# 09-RF_SUBG.net
KiCad netlist of a schematic drawn in Altium Designer
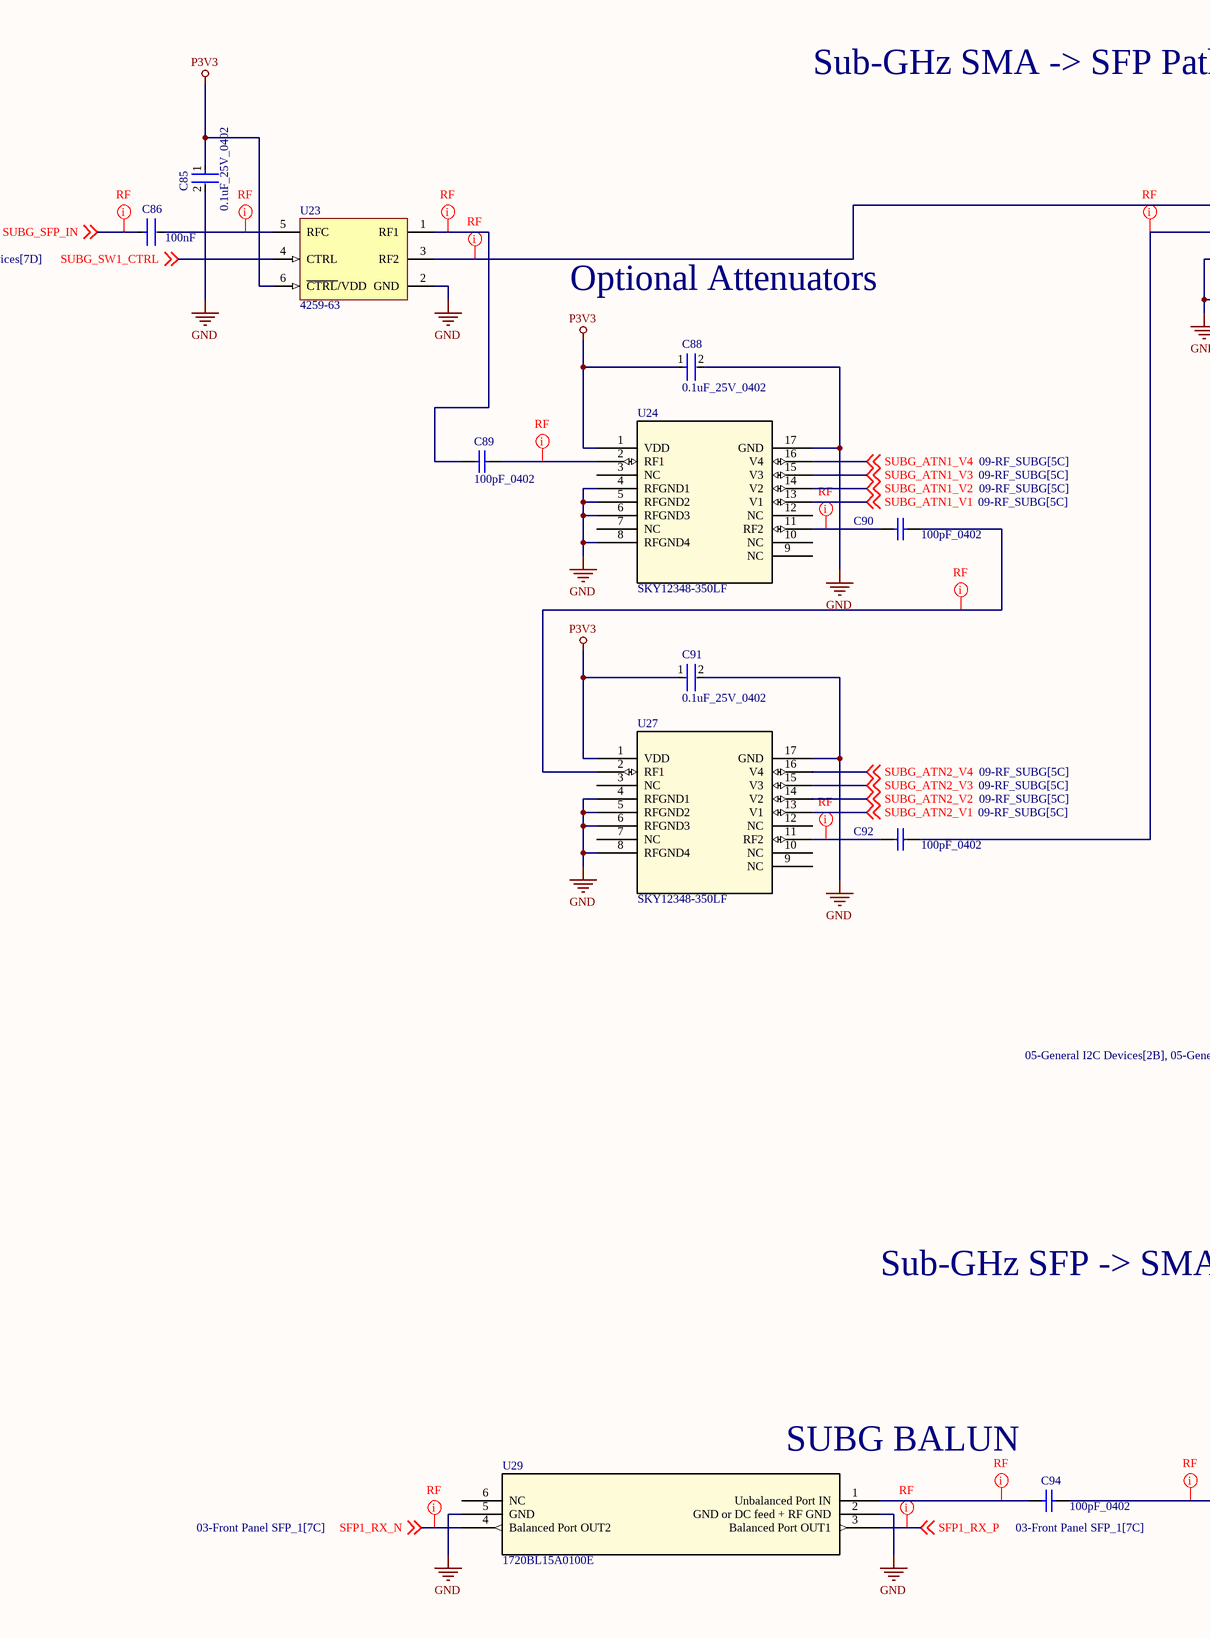
[diagram p0: 09-RF_SUBG.SchDoc, left]
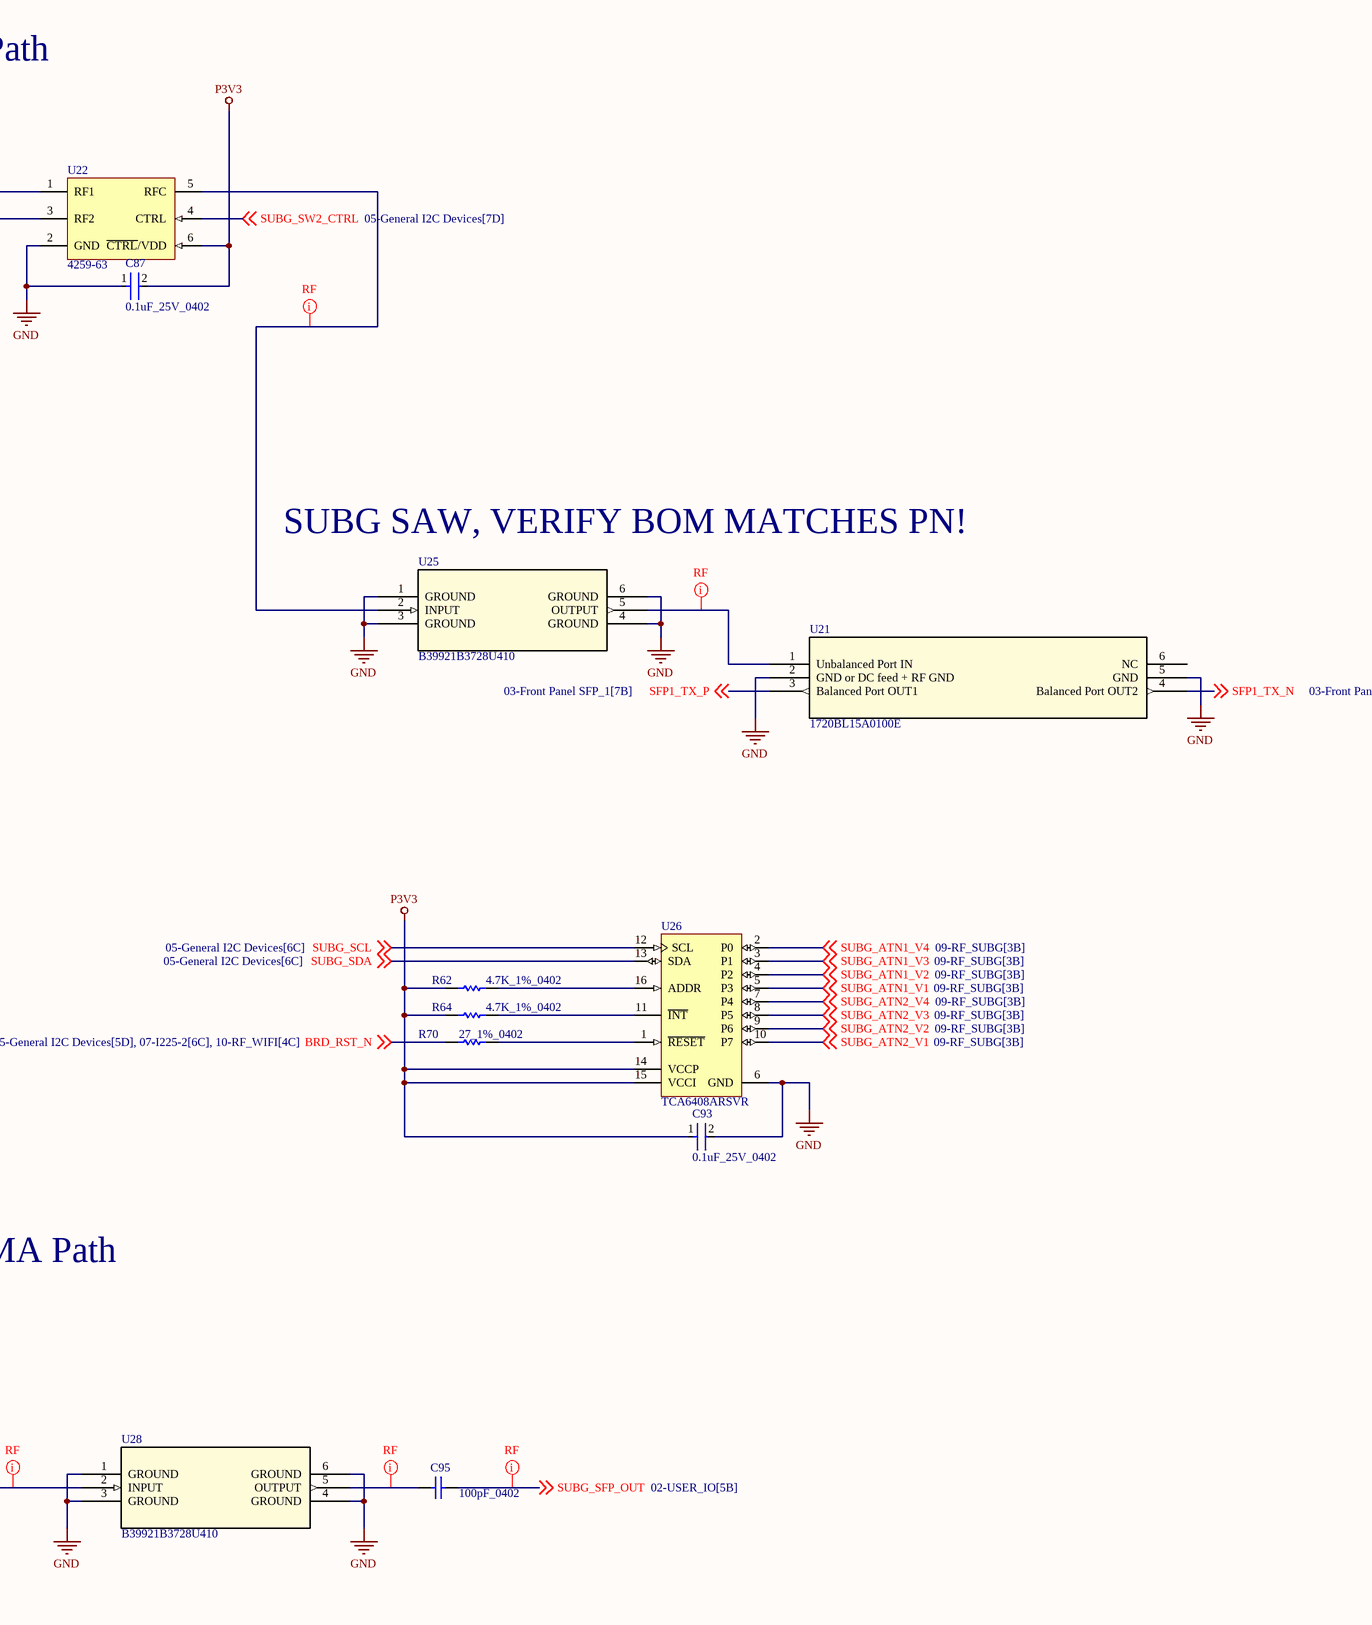
[diagram p1: 09-RF_SUBG.SchDoc, right]

(export (version "E")
  (design (tool "Eeschema 10.0.6"))
  (components
    (comp (ref "C85")
      (value "0.1uF_25V_0402")
      (footprint "FP-0402-L_1_0_1-W_0_5_0_1-IPC_C")
      (description "General Purpose Ceramic Capacitor, 0402, 100nF, 10%, X7R, 15%, 25V")
      (fields (field (name "VOLTAGE") "25V") (field (name "TOLERANCE") "10%"))
      (libsource (lib "Altium Content Vault") (part "b4654b650e69147ec39a6b967a45e02"))
    )
    (comp (ref "C86")
      (value "100nF")
      (footprint "FP-0402-L_1_0_0_05-W_0_5-IPC_B")
      (description "None")
      (fields (field (name "TOLERANCE") "10%"))
      (libsource (lib "") (part "b4654b650e69147ec39a6b967a45e02_1"))
    )
    (comp (ref "C87")
      (value "0.1uF_25V_0402")
      (footprint "FP-0402-L_1_0_1-W_0_5_0_1-IPC_C")
      (description "General Purpose Ceramic Capacitor, 0402, 100nF, 10%, X7R, 15%, 25V")
      (fields (field (name "VOLTAGE") "25V") (field (name "TOLERANCE") "10%"))
      (libsource (lib "Altium Content Vault") (part "b4654b650e69147ec39a6b967a45e02"))
    )
    (comp (ref "C88")
      (value "0.1uF_25V_0402")
      (footprint "FP-0402-L_1_0_1-W_0_5_0_1-IPC_C")
      (description "General Purpose Ceramic Capacitor, 0402, 100nF, 10%, X7R, 15%, 25V")
      (fields (field (name "VOLTAGE") "25V") (field (name "TOLERANCE") "10%"))
      (libsource (lib "Altium Content Vault") (part "b4654b650e69147ec39a6b967a45e02"))
    )
    (comp (ref "C89")
      (value "100pF_0402")
      (footprint "CAPC1005X55X25ML05T10")
      (fields (field (name "MANUFACTURER") "Murata") (field (name "PART NUMBER") "GRM1555C1H101JA01D"))
      (libsource (lib "Altium Content Vault") (part "CAP"))
    )
    (comp (ref "C90")
      (value "100pF_0402")
      (footprint "CAPC1005X55X25ML05T10")
      (fields (field (name "MANUFACTURER") "Murata") (field (name "PART NUMBER") "GRM1555C1H101JA01D"))
      (libsource (lib "Altium Content Vault") (part "CAP"))
    )
    (comp (ref "C91")
      (value "0.1uF_25V_0402")
      (footprint "FP-0402-L_1_0_1-W_0_5_0_1-IPC_C")
      (description "General Purpose Ceramic Capacitor, 0402, 100nF, 10%, X7R, 15%, 25V")
      (fields (field (name "VOLTAGE") "25V") (field (name "TOLERANCE") "10%"))
      (libsource (lib "Altium Content Vault") (part "b4654b650e69147ec39a6b967a45e02"))
    )
    (comp (ref "C92")
      (value "100pF_0402")
      (footprint "CAPC1005X55X25ML05T10")
      (fields (field (name "MANUFACTURER") "Murata") (field (name "PART NUMBER") "GRM1555C1H101JA01D"))
      (libsource (lib "Altium Content Vault") (part "CAP"))
    )
    (comp (ref "C93")
      (value "0.1uF_25V_0402")
      (footprint "FP-0402-L_1_0_1-W_0_5_0_1-IPC_C")
      (description "General Purpose Ceramic Capacitor, 0402, 100nF, 10%, X7R, 15%, 25V")
      (fields (field (name "VOLTAGE") "25V") (field (name "TOLERANCE") "10%"))
      (libsource (lib "Altium Content Vault") (part "b4654b650e69147ec39a6b967a45e02"))
    )
    (comp (ref "C94")
      (value "100pF_0402")
      (footprint "CAPC1005X55X25ML05T10")
      (fields (field (name "MANUFACTURER") "Murata") (field (name "PART NUMBER") "GRM1555C1H101JA01D"))
      (libsource (lib "Altium Content Vault") (part "CAP"))
    )
    (comp (ref "C95")
      (value "100pF_0402")
      (footprint "CAPC1005X55X25ML05T10")
      (fields (field (name "MANUFACTURER") "Murata") (field (name "PART NUMBER") "GRM1555C1H101JA01D"))
      (libsource (lib "Altium Content Vault") (part "CAP"))
    )
    (comp (ref "R62")
      (value "4.7K_1%_0402")
      (footprint "RESC1005X40X25NL10T10")
      (fields (field (name "MANUFACTURER") "Bourns") (field (name "PART NUMBER") "CR0402-FX-4701GLF"))
      (libsource (lib "Altium Content Vault") (part "RES"))
    )
    (comp (ref "R64")
      (value "4.7K_1%_0402")
      (footprint "RESC1005X40X25NL10T10")
      (fields (field (name "MANUFACTURER") "Bourns") (field (name "PART NUMBER") "CR0402-FX-4701GLF"))
      (libsource (lib "Altium Content Vault") (part "RES"))
    )
    (comp (ref "R70")
      (value "27_1%_0402")
      (footprint "RESC1005X40X25NL05T05")
      (fields (field (name "PART NUMBER") "CRCW040227R0FKED") (field (name "MANUFACTURER") "Vishay Dale"))
      (libsource (lib "Altium Content Vault") (part "RES"))
    )
    (comp (ref "U21")
      (value "1720BL15A0100E")
      (footprint "SMT_15B0050E_JOT")
      (description "No Description Available")
      (libsource (lib "") (part "1720BL15A0100E_1"))
    )
    (comp (ref "U22")
      (value "4259-63")
      (footprint "PERE-SC-70-6_M")
      (description "IC RF Switch SPDT, 50 Ohm, 6-Pin SC70, RoHS, Tape and Reel")
      (fields (field (name "MANUFACTURER") "Peregrine Semiconductor"))
      (libsource (lib "Altium Content Vault") (part "PERE-PE4259-6"))
    )
    (comp (ref "U23")
      (value "4259-63")
      (footprint "PERE-SC-70-6_M")
      (description "IC RF Switch SPDT, 50 Ohm, 6-Pin SC70, RoHS, Tape and Reel")
      (fields (field (name "MANUFACTURER") "Peregrine Semiconductor"))
      (libsource (lib "") (part "PERE-PE4259-6_1"))
    )
    (comp (ref "U24")
      (value "SKY12348-350LF")
      (footprint "SKY12348-350LF_SKY")
      (description "No Description Available")
      (libsource (lib "SKY12348-350LF") (part "SKY12348-350LF"))
    )
    (comp (ref "U25")
      (value "B39921B3728U410")
      (footprint "B39162B3913U410_QUA")
      (description "No Description Available")
      (libsource (lib "B39162B3913U410") (part "B39162B3913U410"))
    )
    (comp (ref "U26")
      (value "TCA6408ARSVR")
      (footprint "RSV0016A_V")
      (fields (field (name "MANUFACTURER") "Texas Instruments"))
      (libsource (lib "Altium Content Vault") (part "TI-TCA6408A-UQFN_RSV-16"))
    )
    (comp (ref "U27")
      (value "SKY12348-350LF")
      (footprint "SKY12348-350LF_SKY")
      (description "No Description Available")
      (libsource (lib "SKY12348-350LF") (part "SKY12348-350LF"))
    )
    (comp (ref "U28")
      (value "B39921B3728U410")
      (footprint "B39162B3913U410_QUA")
      (description "No Description Available")
      (libsource (lib "B39162B3913U410") (part "B39162B3913U410"))
    )
    (comp (ref "U29")
      (value "1720BL15A0100E")
      (footprint "SMT_15B0050E_JOT")
      (description "No Description Available")
      (libsource (lib "1720BL15A0100E") (part "1720BL15A0100E"))
    )
  )
  (nets
    (net (code "1") (name "BRD_RST_N") (class "Default")
      (node (ref "R70") (pin "1") (pinfunction "1_1") (pintype "passive"))
    )
    (net (code "2") (name "GND") (class "Default")
      (node (ref "C85") (pin "2") (pinfunction "2_2") (pintype "passive"))
      (node (ref "C87") (pin "1") (pinfunction "1_1") (pintype "passive"))
      (node (ref "C88") (pin "2") (pinfunction "2_2") (pintype "passive"))
      (node (ref "C91") (pin "2") (pinfunction "2_2") (pintype "passive"))
      (node (ref "C93") (pin "2") (pinfunction "2_2") (pintype "passive"))
      (node (ref "U21") (pin "2") (pinfunction "GND_or_DC_feed_+_RF_GND_2") (pintype "power_in"))
      (node (ref "U21") (pin "5") (pinfunction "GND_5") (pintype "power_in"))
      (node (ref "U22") (pin "2") (pinfunction "GND_2") (pintype "power_in"))
      (node (ref "U23") (pin "2") (pinfunction "GND_2") (pintype "power_in"))
      (node (ref "U24") (pin "17") (pinfunction "GND_17") (pintype "power_in"))
      (node (ref "U24") (pin "4") (pinfunction "RFGND1_4") (pintype "power_in"))
      (node (ref "U24") (pin "5") (pinfunction "RFGND2_5") (pintype "power_in"))
      (node (ref "U24") (pin "6") (pinfunction "RFGND3_6") (pintype "power_in"))
      (node (ref "U24") (pin "8") (pinfunction "RFGND4_8") (pintype "power_in"))
      (node (ref "U25") (pin "1") (pinfunction "GROUND_1") (pintype "power_in"))
      (node (ref "U25") (pin "3") (pinfunction "GROUND_3") (pintype "power_in"))
      (node (ref "U25") (pin "4") (pinfunction "GROUND_4") (pintype "power_in"))
      (node (ref "U25") (pin "6") (pinfunction "GROUND_6") (pintype "power_in"))
      (node (ref "U26") (pin "6") (pinfunction "GND_6") (pintype "power_in"))
      (node (ref "U27") (pin "17") (pinfunction "GND_17") (pintype "power_in"))
      (node (ref "U27") (pin "4") (pinfunction "RFGND1_4") (pintype "power_in"))
      (node (ref "U27") (pin "5") (pinfunction "RFGND2_5") (pintype "power_in"))
      (node (ref "U27") (pin "6") (pinfunction "RFGND3_6") (pintype "power_in"))
      (node (ref "U27") (pin "8") (pinfunction "RFGND4_8") (pintype "power_in"))
      (node (ref "U28") (pin "1") (pinfunction "GROUND_1") (pintype "power_in"))
      (node (ref "U28") (pin "3") (pinfunction "GROUND_3") (pintype "power_in"))
      (node (ref "U28") (pin "4") (pinfunction "GROUND_4") (pintype "power_in"))
      (node (ref "U28") (pin "6") (pinfunction "GROUND_6") (pintype "power_in"))
      (node (ref "U29") (pin "2") (pinfunction "GND_or_DC_feed_+_RF_GND_2") (pintype "power_in"))
      (node (ref "U29") (pin "5") (pinfunction "GND_5") (pintype "power_in"))
    )
    (net (code "3") (name "Net-(U21-Unbalanced_Port_IN)") (class "Default")
      (node (ref "U21") (pin "1") (pinfunction "Unbalanced_Port_IN_1") (pintype "passive"))
      (node (ref "U25") (pin "5") (pinfunction "OUTPUT_5") (pintype "output"))
    )
    (net (code "4") (name "Net-(U22-RF1)") (class "Default")
      (node (ref "U22") (pin "1") (pinfunction "RF1_1") (pintype "passive"))
      (node (ref "U23") (pin "3") (pinfunction "RF2_3") (pintype "passive"))
    )
    (net (code "5") (name "Net-(U22-RF2)") (class "Default")
      (node (ref "C92") (pin "2") (pinfunction "2_2") (pintype "passive"))
      (node (ref "U22") (pin "3") (pinfunction "RF2_3") (pintype "passive"))
    )
    (net (code "6") (name "Net-(U22-RFC)") (class "Default")
      (node (ref "U22") (pin "5") (pinfunction "RFC_5") (pintype "passive"))
      (node (ref "U25") (pin "2") (pinfunction "INPUT_2") (pintype "input"))
    )
    (net (code "7") (name "Net-(U23-RF1)") (class "Default")
      (node (ref "C89") (pin "1") (pinfunction "1_1") (pintype "passive"))
      (node (ref "U23") (pin "1") (pinfunction "RF1_1") (pintype "passive"))
    )
    (net (code "8") (name "Net-(U23-RFC)") (class "Default")
      (node (ref "C86") (pin "2") (pinfunction "2_2") (pintype "passive"))
      (node (ref "U23") (pin "5") (pinfunction "RFC_5") (pintype "passive"))
    )
    (net (code "9") (name "Net-(U24-RF1)") (class "Default")
      (node (ref "C89") (pin "2") (pinfunction "2_2") (pintype "passive"))
      (node (ref "U24") (pin "2") (pinfunction "RF1_2") (pintype "bidirectional"))
    )
    (net (code "10") (name "Net-(U24-RF2)") (class "Default")
      (node (ref "C90") (pin "1") (pinfunction "1_1") (pintype "passive"))
      (node (ref "U24") (pin "11") (pinfunction "RF2_11") (pintype "bidirectional"))
    )
    (net (code "11") (name "Net-(U26-ADDR)") (class "Default")
      (node (ref "R62") (pin "1") (pinfunction "1_1") (pintype "passive"))
      (node (ref "U26") (pin "16") (pinfunction "ADDR_16") (pintype "input"))
    )
    (net (code "12") (name "Net-(U26-~{INT})") (class "Default")
      (node (ref "R64") (pin "1") (pinfunction "1_1") (pintype "passive"))
      (node (ref "U26") (pin "11") (pinfunction "~{INT}_11") (pintype "open_collector"))
    )
    (net (code "13") (name "Net-(U26-~{RESET})") (class "Default")
      (node (ref "R70") (pin "2") (pinfunction "2_2") (pintype "passive"))
      (node (ref "U26") (pin "1") (pinfunction "~{RESET}_1") (pintype "input"))
    )
    (net (code "14") (name "Net-(U27-RF1)") (class "Default")
      (node (ref "C90") (pin "2") (pinfunction "2_2") (pintype "passive"))
      (node (ref "U27") (pin "2") (pinfunction "RF1_2") (pintype "bidirectional"))
    )
    (net (code "15") (name "Net-(U27-RF2)") (class "Default")
      (node (ref "C92") (pin "1") (pinfunction "1_1") (pintype "passive"))
      (node (ref "U27") (pin "11") (pinfunction "RF2_11") (pintype "bidirectional"))
    )
    (net (code "16") (name "Net-(U28-INPUT)") (class "Default")
      (node (ref "C94") (pin "2") (pinfunction "2_2") (pintype "passive"))
      (node (ref "U28") (pin "2") (pinfunction "INPUT_2") (pintype "input"))
    )
    (net (code "17") (name "Net-(U28-OUTPUT)") (class "Default")
      (node (ref "C95") (pin "1") (pinfunction "1_1") (pintype "passive"))
      (node (ref "U28") (pin "5") (pinfunction "OUTPUT_5") (pintype "output"))
    )
    (net (code "18") (name "Net-(U29-Unbalanced_Port_IN)") (class "Default")
      (node (ref "C94") (pin "1") (pinfunction "1_1") (pintype "passive"))
      (node (ref "U29") (pin "1") (pinfunction "Unbalanced_Port_IN_1") (pintype "passive"))
    )
    (net (code "19") (name "P3V3") (class "Default")
      (node (ref "C85") (pin "1") (pinfunction "1_1") (pintype "passive"))
      (node (ref "C87") (pin "2") (pinfunction "2_2") (pintype "passive"))
      (node (ref "C88") (pin "1") (pinfunction "1_1") (pintype "passive"))
      (node (ref "C91") (pin "1") (pinfunction "1_1") (pintype "passive"))
      (node (ref "C93") (pin "1") (pinfunction "1_1") (pintype "passive"))
      (node (ref "R62") (pin "2") (pinfunction "2_2") (pintype "passive"))
      (node (ref "R64") (pin "2") (pinfunction "2_2") (pintype "passive"))
      (node (ref "U22") (pin "6") (pinfunction "~{CTRL}/VDD_6") (pintype "input"))
      (node (ref "U23") (pin "6") (pinfunction "~{CTRL}/VDD_6") (pintype "input"))
      (node (ref "U24") (pin "1") (pinfunction "VDD_1") (pintype "power_in"))
      (node (ref "U26") (pin "14") (pinfunction "VCCP_14") (pintype "power_in"))
      (node (ref "U26") (pin "15") (pinfunction "VCCI_15") (pintype "power_in"))
      (node (ref "U27") (pin "1") (pinfunction "VDD_1") (pintype "power_in"))
    )
    (net (code "20") (name "SFP1_RX_N") (class "Default")
      (node (ref "U29") (pin "4") (pinfunction "Balanced_Port_OUT2_4") (pintype "output"))
    )
    (net (code "21") (name "SFP1_RX_P") (class "Default")
      (node (ref "U29") (pin "3") (pinfunction "Balanced_Port_OUT1_3") (pintype "output"))
    )
    (net (code "22") (name "SFP1_TX_N") (class "Default")
      (node (ref "U21") (pin "4") (pinfunction "Balanced_Port_OUT2_4") (pintype "output"))
    )
    (net (code "23") (name "SFP1_TX_P") (class "Default")
      (node (ref "U21") (pin "3") (pinfunction "Balanced_Port_OUT1_3") (pintype "output"))
    )
    (net (code "24") (name "SUBG_ATN1_V1") (class "Default")
      (node (ref "U24") (pin "13") (pinfunction "V1_13") (pintype "bidirectional"))
      (node (ref "U26") (pin "5") (pinfunction "P3_5") (pintype "bidirectional"))
    )
    (net (code "25") (name "SUBG_ATN1_V2") (class "Default")
      (node (ref "U24") (pin "14") (pinfunction "V2_14") (pintype "bidirectional"))
      (node (ref "U26") (pin "4") (pinfunction "P2_4") (pintype "bidirectional"))
    )
    (net (code "26") (name "SUBG_ATN1_V3") (class "Default")
      (node (ref "U24") (pin "15") (pinfunction "V3_15") (pintype "bidirectional"))
      (node (ref "U26") (pin "3") (pinfunction "P1_3") (pintype "bidirectional"))
    )
    (net (code "27") (name "SUBG_ATN1_V4") (class "Default")
      (node (ref "U24") (pin "16") (pinfunction "V4_16") (pintype "bidirectional"))
      (node (ref "U26") (pin "2") (pinfunction "P0_2") (pintype "bidirectional"))
    )
    (net (code "28") (name "SUBG_ATN2_V1") (class "Default")
      (node (ref "U26") (pin "10") (pinfunction "P7_10") (pintype "bidirectional"))
      (node (ref "U27") (pin "13") (pinfunction "V1_13") (pintype "bidirectional"))
    )
    (net (code "29") (name "SUBG_ATN2_V2") (class "Default")
      (node (ref "U26") (pin "9") (pinfunction "P6_9") (pintype "bidirectional"))
      (node (ref "U27") (pin "14") (pinfunction "V2_14") (pintype "bidirectional"))
    )
    (net (code "30") (name "SUBG_ATN2_V3") (class "Default")
      (node (ref "U26") (pin "8") (pinfunction "P5_8") (pintype "bidirectional"))
      (node (ref "U27") (pin "15") (pinfunction "V3_15") (pintype "bidirectional"))
    )
    (net (code "31") (name "SUBG_ATN2_V4") (class "Default")
      (node (ref "U26") (pin "7") (pinfunction "P4_7") (pintype "bidirectional"))
      (node (ref "U27") (pin "16") (pinfunction "V4_16") (pintype "bidirectional"))
    )
    (net (code "32") (name "SUBG_SCL") (class "Default")
      (node (ref "U26") (pin "12") (pinfunction "SCL_12") (pintype "input"))
    )
    (net (code "33") (name "SUBG_SDA") (class "Default")
      (node (ref "U26") (pin "13") (pinfunction "SDA_13") (pintype "bidirectional"))
    )
    (net (code "34") (name "SUBG_SFP_IN") (class "Default")
      (node (ref "C86") (pin "1") (pinfunction "1_1") (pintype "passive"))
    )
    (net (code "35") (name "SUBG_SFP_OUT") (class "Default")
      (node (ref "C95") (pin "2") (pinfunction "2_2") (pintype "passive"))
    )
    (net (code "36") (name "SUBG_SW1_CTRL") (class "Default")
      (node (ref "U23") (pin "4") (pinfunction "CTRL_4") (pintype "input"))
    )
    (net (code "37") (name "SUBG_SW2_CTRL") (class "Default")
      (node (ref "U22") (pin "4") (pinfunction "CTRL_4") (pintype "input"))
    )
    (net (code "38") (name "unconnected-(U21-NC-Pad6)") (class "Default")
      (node (ref "U21") (pin "6") (pinfunction "NC_6") (pintype "passive"))
    )
    (net (code "39") (name "unconnected-(U24-NC-Pad3)") (class "Default")
      (node (ref "U24") (pin "3") (pinfunction "NC_3") (pintype "passive"))
    )
    (net (code "40") (name "unconnected-(U24-NC-Pad7)") (class "Default")
      (node (ref "U24") (pin "7") (pinfunction "NC_7") (pintype "passive"))
    )
    (net (code "41") (name "unconnected-(U24-NC-Pad9)") (class "Default")
      (node (ref "U24") (pin "9") (pinfunction "NC_9") (pintype "passive"))
    )
    (net (code "42") (name "unconnected-(U24-NC-Pad10)") (class "Default")
      (node (ref "U24") (pin "10") (pinfunction "NC_10") (pintype "passive"))
    )
    (net (code "43") (name "unconnected-(U24-NC-Pad12)") (class "Default")
      (node (ref "U24") (pin "12") (pinfunction "NC_12") (pintype "passive"))
    )
    (net (code "44") (name "unconnected-(U27-NC-Pad3)") (class "Default")
      (node (ref "U27") (pin "3") (pinfunction "NC_3") (pintype "passive"))
    )
    (net (code "45") (name "unconnected-(U27-NC-Pad7)") (class "Default")
      (node (ref "U27") (pin "7") (pinfunction "NC_7") (pintype "passive"))
    )
    (net (code "46") (name "unconnected-(U27-NC-Pad9)") (class "Default")
      (node (ref "U27") (pin "9") (pinfunction "NC_9") (pintype "passive"))
    )
    (net (code "47") (name "unconnected-(U27-NC-Pad10)") (class "Default")
      (node (ref "U27") (pin "10") (pinfunction "NC_10") (pintype "passive"))
    )
    (net (code "48") (name "unconnected-(U27-NC-Pad12)") (class "Default")
      (node (ref "U27") (pin "12") (pinfunction "NC_12") (pintype "passive"))
    )
    (net (code "49") (name "unconnected-(U29-NC-Pad6)") (class "Default")
      (node (ref "U29") (pin "6") (pinfunction "NC_6") (pintype "passive"))
    )
  )
)
